# RS232.net
KiCad netlist of a schematic drawn in Altium Designer
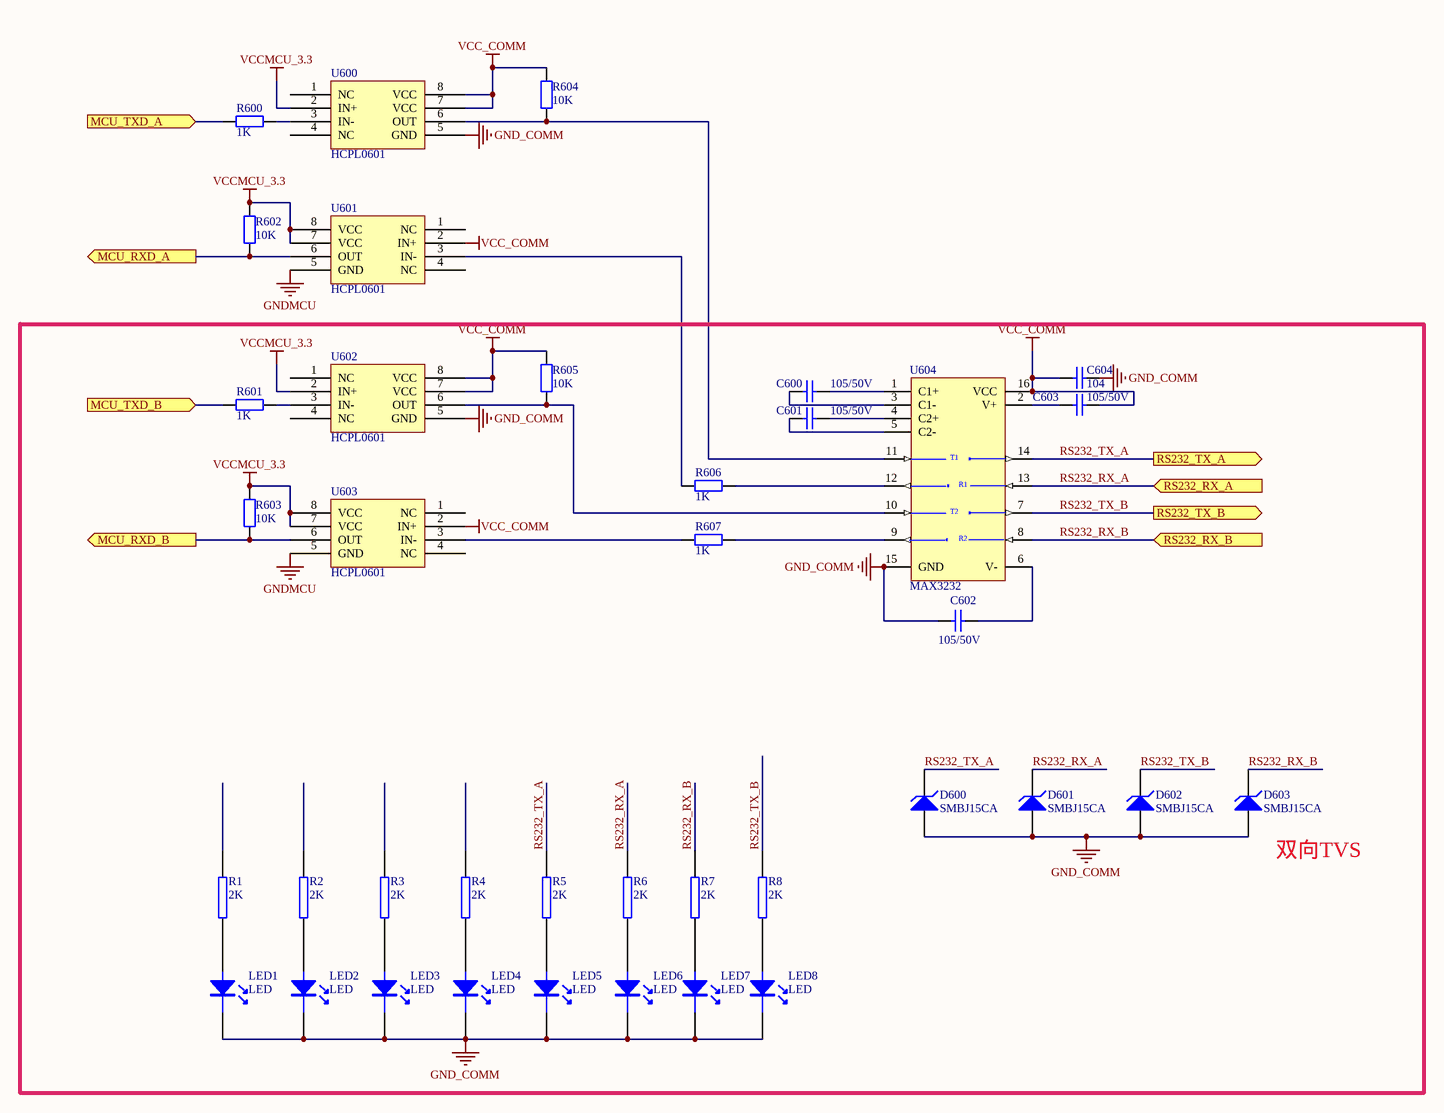
[diagram p0: RS232.SchDoc]

(export (version "E")
  (design (tool "Eeschema 10.0.6"))
  (components
    (comp (ref "C600")
      (value "105/50V")
      (footprint "0805/C2")
      (description "Capacitor")
      (fields (field (name "PUBLISHER") "Altium Limited"))
      (libsource (lib "YGInfoSCHLib") (part "Cap"))
    )
    (comp (ref "C601")
      (value "105/50V")
      (footprint "0805/C2")
      (description "Capacitor")
      (fields (field (name "PUBLISHER") "Altium Limited"))
      (libsource (lib "YGInfoSCHLib") (part "Cap"))
    )
    (comp (ref "C602")
      (value "105/50V")
      (footprint "0805/C2")
      (description "Capacitor")
      (fields (field (name "PUBLISHER") "Altium Limited"))
      (libsource (lib "YGInfoSCHLib") (part "Cap"))
    )
    (comp (ref "C603")
      (value "105/50V")
      (footprint "0805/C2")
      (description "Capacitor")
      (fields (field (name "PUBLISHER") "Altium Limited"))
      (libsource (lib "YGInfoSCHLib") (part "Cap"))
    )
    (comp (ref "C604")
      (value "104")
      (footprint "0805/C2")
      (description "Capacitor")
      (fields (field (name "PUBLISHER") "Altium Limited"))
      (libsource (lib "YGInfoSCHLib") (part "Cap"))
    )
    (comp (ref "D600")
      (value "SMBJ15CA")
      (footprint "SMB")
      (description "Zener Diode")
      (fields (field (name "PUBLISHER") "Altium Limited"))
      (libsource (lib "YGInfoSCHLib") (part "D Zener"))
    )
    (comp (ref "D601")
      (value "SMBJ15CA")
      (footprint "SMB")
      (description "Zener Diode")
      (fields (field (name "PUBLISHER") "Altium Limited"))
      (libsource (lib "YGInfoSCHLib") (part "D Zener"))
    )
    (comp (ref "D602")
      (value "SMBJ15CA")
      (footprint "SMB")
      (description "Zener Diode")
      (fields (field (name "PUBLISHER") "Altium Limited"))
      (libsource (lib "YGInfoSCHLib") (part "D Zener"))
    )
    (comp (ref "D603")
      (value "SMBJ15CA")
      (footprint "SMB")
      (description "Zener Diode")
      (fields (field (name "PUBLISHER") "Altium Limited"))
      (libsource (lib "YGInfoSCHLib") (part "D Zener"))
    )
    (comp (ref "LED1") (value "LED") (footprint "LED0805") (libsource (lib "*") (part "LED-PH")))
    (comp (ref "LED2") (value "LED") (footprint "LED0805") (libsource (lib "*") (part "LED-PH")))
    (comp (ref "LED3") (value "LED") (footprint "LED0805") (libsource (lib "*") (part "LED-PH")))
    (comp (ref "LED4") (value "LED") (footprint "LED0805") (libsource (lib "*") (part "LED-PH")))
    (comp (ref "LED5") (value "LED") (footprint "LED0805") (libsource (lib "*") (part "LED-PH")))
    (comp (ref "LED6") (value "LED") (footprint "LED0805") (libsource (lib "*") (part "LED-PH")))
    (comp (ref "LED7") (value "LED") (footprint "LED0805") (libsource (lib "YGInfoSCHLib") (part "LED-PH")))
    (comp (ref "LED8") (value "LED") (footprint "LED0805") (libsource (lib "YGInfoSCHLib") (part "LED-PH")))
    (comp (ref "R1") (value "2K") (footprint "0805/R2") (libsource (lib "*") (part "RES2")))
    (comp (ref "R2") (value "2K") (footprint "0805/R2") (libsource (lib "*") (part "RES2")))
    (comp (ref "R3") (value "2K") (footprint "0805/R2") (libsource (lib "*") (part "RES2")))
    (comp (ref "R4") (value "2K") (footprint "0805/R2") (libsource (lib "*") (part "RES2")))
    (comp (ref "R5") (value "2K") (footprint "0805/R2") (libsource (lib "*") (part "RES2")))
    (comp (ref "R6") (value "2K") (footprint "0805/R2") (libsource (lib "*") (part "RES2")))
    (comp (ref "R7") (value "2K") (footprint "0805/R2") (libsource (lib "YGInfoSCHLib") (part "RES2")))
    (comp (ref "R8") (value "2K") (footprint "0805/R2") (libsource (lib "YGInfoSCHLib") (part "RES2")))
    (comp (ref "R600") (value "1K") (footprint "0805/R2") (libsource (lib "YGInfoSCHLib") (part "RES1")))
    (comp (ref "R601") (value "1K") (footprint "0805/R2") (libsource (lib "YGInfoSCHLib") (part "RES1")))
    (comp (ref "R602") (value "10K") (footprint "0805/R2") (libsource (lib "YGInfoSCHLib") (part "RES1")))
    (comp (ref "R603") (value "10K") (footprint "0805/R2") (libsource (lib "YGInfoSCHLib") (part "RES1")))
    (comp (ref "R604") (value "10K") (footprint "0805/R2") (libsource (lib "") (part "RES1_1")))
    (comp (ref "R605") (value "10K") (footprint "0805/R2") (libsource (lib "") (part "RES1_1")))
    (comp (ref "R606") (value "1K") (footprint "0805/R2") (libsource (lib "YGInfoSCHLib") (part "RES1")))
    (comp (ref "R607")
      (value "1K")
      (footprint "RESC_E0805_2012X50N")
      (libsource (lib "YGInfoSCHLib") (part "RES1"))
    )
    (comp (ref "U600") (value "HCPL0601") (footprint "HCPL0601") (libsource (lib "") (part "6N137_1")))
    (comp (ref "U601")
      (value "HCPL0601")
      (footprint "HCPL0601")
      (libsource (lib "YGInfoSCHLib") (part "6N137"))
    )
    (comp (ref "U602") (value "HCPL0601") (footprint "HCPL0601") (libsource (lib "") (part "6N137_1")))
    (comp (ref "U603")
      (value "HCPL0601")
      (footprint "HCPL0601")
      (libsource (lib "YGInfoSCHLib") (part "6N137"))
    )
    (comp (ref "U604")
      (value "MAX3232")
      (footprint "SO-16")
      (libsource (lib "YGInfoSCHLib") (part "MAX3232"))
    )
  )
  (nets
    (net (code "1") (name "/MCU_RXD_A") (class "Default")
      (node (ref "R602") (pin "1") (pinfunction "1_1") (pintype "passive"))
      (node (ref "U601") (pin "6") (pinfunction "OUT_6") (pintype "passive"))
    )
    (net (code "2") (name "/MCU_RXD_B") (class "Default")
      (node (ref "R603") (pin "1") (pinfunction "1_1") (pintype "passive"))
      (node (ref "U603") (pin "6") (pinfunction "OUT_6") (pintype "passive"))
    )
    (net (code "3") (name "/MCU_TXD_A") (class "Default")
      (node (ref "R600") (pin "1") (pinfunction "1_1") (pintype "passive"))
    )
    (net (code "4") (name "/MCU_TXD_B") (class "Default")
      (node (ref "R601") (pin "1") (pinfunction "1_1") (pintype "passive"))
    )
    (net (code "5") (name "/RS232_RX_A") (class "Default")
      (node (ref "D601") (pin "2") (pinfunction "K_2") (pintype "passive"))
      (node (ref "R6") (pin "2") (pinfunction "2_2") (pintype "passive"))
      (node (ref "U604") (pin "13") (pinfunction "R1IN_13") (pintype "input"))
    )
    (net (code "6") (name "/RS232_RX_B") (class "Default")
      (node (ref "D603") (pin "2") (pinfunction "K_2") (pintype "passive"))
      (node (ref "R7") (pin "2") (pinfunction "2_2") (pintype "passive"))
      (node (ref "U604") (pin "8") (pinfunction "R2IN_8") (pintype "input"))
    )
    (net (code "7") (name "/RS232_TX_A") (class "Default")
      (node (ref "D600") (pin "2") (pinfunction "K_2") (pintype "passive"))
      (node (ref "R5") (pin "2") (pinfunction "2_2") (pintype "passive"))
      (node (ref "U604") (pin "14") (pinfunction "T1OUT_14") (pintype "output"))
    )
    (net (code "8") (name "/RS232_TX_B") (class "Default")
      (node (ref "D602") (pin "2") (pinfunction "K_2") (pintype "passive"))
      (node (ref "R8") (pin "2") (pinfunction "2_2") (pintype "passive"))
      (node (ref "U604") (pin "7") (pinfunction "T2OUT_7") (pintype "output"))
    )
    (net (code "9") (name "GNDMCU") (class "Default")
      (node (ref "U601") (pin "5") (pinfunction "GND_5") (pintype "passive"))
      (node (ref "U603") (pin "5") (pinfunction "GND_5") (pintype "passive"))
    )
    (net (code "10") (name "GND_COMM") (class "Default")
      (node (ref "C602") (pin "1") (pinfunction "1_1") (pintype "passive"))
      (node (ref "C604") (pin "1") (pinfunction "1_1") (pintype "passive"))
      (node (ref "D600") (pin "1") (pinfunction "A_1") (pintype "passive"))
      (node (ref "D601") (pin "1") (pinfunction "A_1") (pintype "passive"))
      (node (ref "D602") (pin "1") (pinfunction "A_1") (pintype "passive"))
      (node (ref "D603") (pin "1") (pinfunction "A_1") (pintype "passive"))
      (node (ref "LED1") (pin "2") (pinfunction "2_2") (pintype "passive"))
      (node (ref "LED2") (pin "2") (pinfunction "2_2") (pintype "passive"))
      (node (ref "LED3") (pin "2") (pinfunction "2_2") (pintype "passive"))
      (node (ref "LED4") (pin "2") (pinfunction "2_2") (pintype "passive"))
      (node (ref "LED5") (pin "2") (pinfunction "2_2") (pintype "passive"))
      (node (ref "LED6") (pin "2") (pinfunction "2_2") (pintype "passive"))
      (node (ref "LED7") (pin "2") (pinfunction "2_2") (pintype "passive"))
      (node (ref "LED8") (pin "2") (pinfunction "2_2") (pintype "passive"))
      (node (ref "U600") (pin "5") (pinfunction "GND_5") (pintype "passive"))
      (node (ref "U602") (pin "5") (pinfunction "GND_5") (pintype "passive"))
      (node (ref "U604") (pin "15") (pinfunction "GND_15") (pintype "power_in"))
    )
    (net (code "11") (name "Net-(LED1-Pad1)") (class "Default")
      (node (ref "LED1") (pin "1") (pinfunction "1_1") (pintype "passive"))
      (node (ref "R1") (pin "1") (pinfunction "1_1") (pintype "passive"))
    )
    (net (code "12") (name "Net-(LED2-Pad1)") (class "Default")
      (node (ref "LED2") (pin "1") (pinfunction "1_1") (pintype "passive"))
      (node (ref "R2") (pin "1") (pinfunction "1_1") (pintype "passive"))
    )
    (net (code "13") (name "Net-(LED3-Pad1)") (class "Default")
      (node (ref "LED3") (pin "1") (pinfunction "1_1") (pintype "passive"))
      (node (ref "R3") (pin "1") (pinfunction "1_1") (pintype "passive"))
    )
    (net (code "14") (name "Net-(LED4-Pad1)") (class "Default")
      (node (ref "LED4") (pin "1") (pinfunction "1_1") (pintype "passive"))
      (node (ref "R4") (pin "1") (pinfunction "1_1") (pintype "passive"))
    )
    (net (code "15") (name "Net-(LED5-Pad1)") (class "Default")
      (node (ref "LED5") (pin "1") (pinfunction "1_1") (pintype "passive"))
      (node (ref "R5") (pin "1") (pinfunction "1_1") (pintype "passive"))
    )
    (net (code "16") (name "Net-(LED6-Pad1)") (class "Default")
      (node (ref "LED6") (pin "1") (pinfunction "1_1") (pintype "passive"))
      (node (ref "R6") (pin "1") (pinfunction "1_1") (pintype "passive"))
    )
    (net (code "17") (name "Net-(LED7-Pad1)") (class "Default")
      (node (ref "LED7") (pin "1") (pinfunction "1_1") (pintype "passive"))
      (node (ref "R7") (pin "1") (pinfunction "1_1") (pintype "passive"))
    )
    (net (code "18") (name "Net-(LED8-Pad1)") (class "Default")
      (node (ref "LED8") (pin "1") (pinfunction "1_1") (pintype "passive"))
      (node (ref "R8") (pin "1") (pinfunction "1_1") (pintype "passive"))
    )
    (net (code "19") (name "Net-(U600-IN-)") (class "Default")
      (node (ref "R600") (pin "2") (pinfunction "2_2") (pintype "passive"))
      (node (ref "U600") (pin "3") (pinfunction "IN-_3") (pintype "passive"))
    )
    (net (code "20") (name "Net-(U600-OUT)") (class "Default")
      (node (ref "R604") (pin "1") (pinfunction "1_1") (pintype "passive"))
      (node (ref "U600") (pin "6") (pinfunction "OUT_6") (pintype "passive"))
      (node (ref "U604") (pin "11") (pinfunction "T1IN_11") (pintype "input"))
    )
    (net (code "21") (name "Net-(U601-IN-)") (class "Default")
      (node (ref "R606") (pin "1") (pinfunction "1_1") (pintype "passive"))
      (node (ref "U601") (pin "3") (pinfunction "IN-_3") (pintype "passive"))
    )
    (net (code "22") (name "Net-(U602-IN-)") (class "Default")
      (node (ref "R601") (pin "2") (pinfunction "2_2") (pintype "passive"))
      (node (ref "U602") (pin "3") (pinfunction "IN-_3") (pintype "passive"))
    )
    (net (code "23") (name "Net-(U602-OUT)") (class "Default")
      (node (ref "R605") (pin "1") (pinfunction "1_1") (pintype "passive"))
      (node (ref "U602") (pin "6") (pinfunction "OUT_6") (pintype "passive"))
      (node (ref "U604") (pin "10") (pinfunction "T2IN_10") (pintype "input"))
    )
    (net (code "24") (name "Net-(U603-IN-)") (class "Default")
      (node (ref "R607") (pin "1") (pinfunction "1_1") (pintype "passive"))
      (node (ref "U603") (pin "3") (pinfunction "IN-_3") (pintype "passive"))
    )
    (net (code "25") (name "Net-(U604-C1+)") (class "Default")
      (node (ref "C600") (pin "1") (pinfunction "1_1") (pintype "passive"))
      (node (ref "U604") (pin "1") (pinfunction "C1+_1") (pintype "passive"))
    )
    (net (code "26") (name "Net-(U604-C1-)") (class "Default")
      (node (ref "C600") (pin "2") (pinfunction "2_2") (pintype "passive"))
      (node (ref "U604") (pin "3") (pinfunction "C1-_3") (pintype "passive"))
    )
    (net (code "27") (name "Net-(U604-C2+)") (class "Default")
      (node (ref "C601") (pin "1") (pinfunction "1_1") (pintype "passive"))
      (node (ref "U604") (pin "4") (pinfunction "C2+_4") (pintype "passive"))
    )
    (net (code "28") (name "Net-(U604-C2-)") (class "Default")
      (node (ref "C601") (pin "2") (pinfunction "2_2") (pintype "passive"))
      (node (ref "U604") (pin "5") (pinfunction "C2-_5") (pintype "passive"))
    )
    (net (code "29") (name "Net-(U604-R1OUT)") (class "Default")
      (node (ref "R606") (pin "2") (pinfunction "2_2") (pintype "passive"))
      (node (ref "U604") (pin "12") (pinfunction "R1OUT_12") (pintype "output"))
    )
    (net (code "30") (name "Net-(U604-R2OUT)") (class "Default")
      (node (ref "R607") (pin "2") (pinfunction "2_2") (pintype "passive"))
      (node (ref "U604") (pin "9") (pinfunction "R2OUT_9") (pintype "output"))
    )
    (net (code "31") (name "Net-(U604-V+)") (class "Default")
      (node (ref "C603") (pin "1") (pinfunction "1_1") (pintype "passive"))
      (node (ref "U604") (pin "2") (pinfunction "V+_2") (pintype "power_in"))
    )
    (net (code "32") (name "Net-(U604-V-)") (class "Default")
      (node (ref "C602") (pin "2") (pinfunction "2_2") (pintype "passive"))
      (node (ref "U604") (pin "6") (pinfunction "V-_6") (pintype "power_in"))
    )
    (net (code "33") (name "VCCMCU_3.3") (class "Default")
      (node (ref "R602") (pin "2") (pinfunction "2_2") (pintype "passive"))
      (node (ref "R603") (pin "2") (pinfunction "2_2") (pintype "passive"))
      (node (ref "U600") (pin "2") (pinfunction "IN+_2") (pintype "passive"))
      (node (ref "U601") (pin "7") (pinfunction "VCC_7") (pintype "passive"))
      (node (ref "U601") (pin "8") (pinfunction "VCC_8") (pintype "passive"))
      (node (ref "U602") (pin "2") (pinfunction "IN+_2") (pintype "passive"))
      (node (ref "U603") (pin "7") (pinfunction "VCC_7") (pintype "passive"))
      (node (ref "U603") (pin "8") (pinfunction "VCC_8") (pintype "passive"))
    )
    (net (code "34") (name "VCC_COMM") (class "Default")
      (node (ref "C603") (pin "2") (pinfunction "2_2") (pintype "passive"))
      (node (ref "C604") (pin "2") (pinfunction "2_2") (pintype "passive"))
      (node (ref "R604") (pin "2") (pinfunction "2_2") (pintype "passive"))
      (node (ref "R605") (pin "2") (pinfunction "2_2") (pintype "passive"))
      (node (ref "U600") (pin "7") (pinfunction "VCC_7") (pintype "passive"))
      (node (ref "U600") (pin "8") (pinfunction "VCC_8") (pintype "passive"))
      (node (ref "U601") (pin "2") (pinfunction "IN+_2") (pintype "passive"))
      (node (ref "U602") (pin "7") (pinfunction "VCC_7") (pintype "passive"))
      (node (ref "U602") (pin "8") (pinfunction "VCC_8") (pintype "passive"))
      (node (ref "U603") (pin "2") (pinfunction "IN+_2") (pintype "passive"))
      (node (ref "U604") (pin "16") (pinfunction "VCC_16") (pintype "power_in"))
    )
    (net (code "35") (name "unconnected-(R1-Pad2)") (class "Default")
      (node (ref "R1") (pin "2") (pinfunction "2_2") (pintype "passive"))
    )
    (net (code "36") (name "unconnected-(R2-Pad2)") (class "Default")
      (node (ref "R2") (pin "2") (pinfunction "2_2") (pintype "passive"))
    )
    (net (code "37") (name "unconnected-(R3-Pad2)") (class "Default")
      (node (ref "R3") (pin "2") (pinfunction "2_2") (pintype "passive"))
    )
    (net (code "38") (name "unconnected-(R4-Pad2)") (class "Default")
      (node (ref "R4") (pin "2") (pinfunction "2_2") (pintype "passive"))
    )
    (net (code "39") (name "unconnected-(U600-NC-Pad1)") (class "Default")
      (node (ref "U600") (pin "1") (pinfunction "NC_1") (pintype "passive"))
    )
    (net (code "40") (name "unconnected-(U600-NC-Pad4)") (class "Default")
      (node (ref "U600") (pin "4") (pinfunction "NC_4") (pintype "passive"))
    )
    (net (code "41") (name "unconnected-(U601-NC-Pad1)") (class "Default")
      (node (ref "U601") (pin "1") (pinfunction "NC_1") (pintype "passive"))
    )
    (net (code "42") (name "unconnected-(U601-NC-Pad4)") (class "Default")
      (node (ref "U601") (pin "4") (pinfunction "NC_4") (pintype "passive"))
    )
    (net (code "43") (name "unconnected-(U602-NC-Pad1)") (class "Default")
      (node (ref "U602") (pin "1") (pinfunction "NC_1") (pintype "passive"))
    )
    (net (code "44") (name "unconnected-(U602-NC-Pad4)") (class "Default")
      (node (ref "U602") (pin "4") (pinfunction "NC_4") (pintype "passive"))
    )
    (net (code "45") (name "unconnected-(U603-NC-Pad1)") (class "Default")
      (node (ref "U603") (pin "1") (pinfunction "NC_1") (pintype "passive"))
    )
    (net (code "46") (name "unconnected-(U603-NC-Pad4)") (class "Default")
      (node (ref "U603") (pin "4") (pinfunction "NC_4") (pintype "passive"))
    )
  )
)
